# encoder_amplifier2_1layer.net
KiCad netlist of a schematic drawn in EAGLE
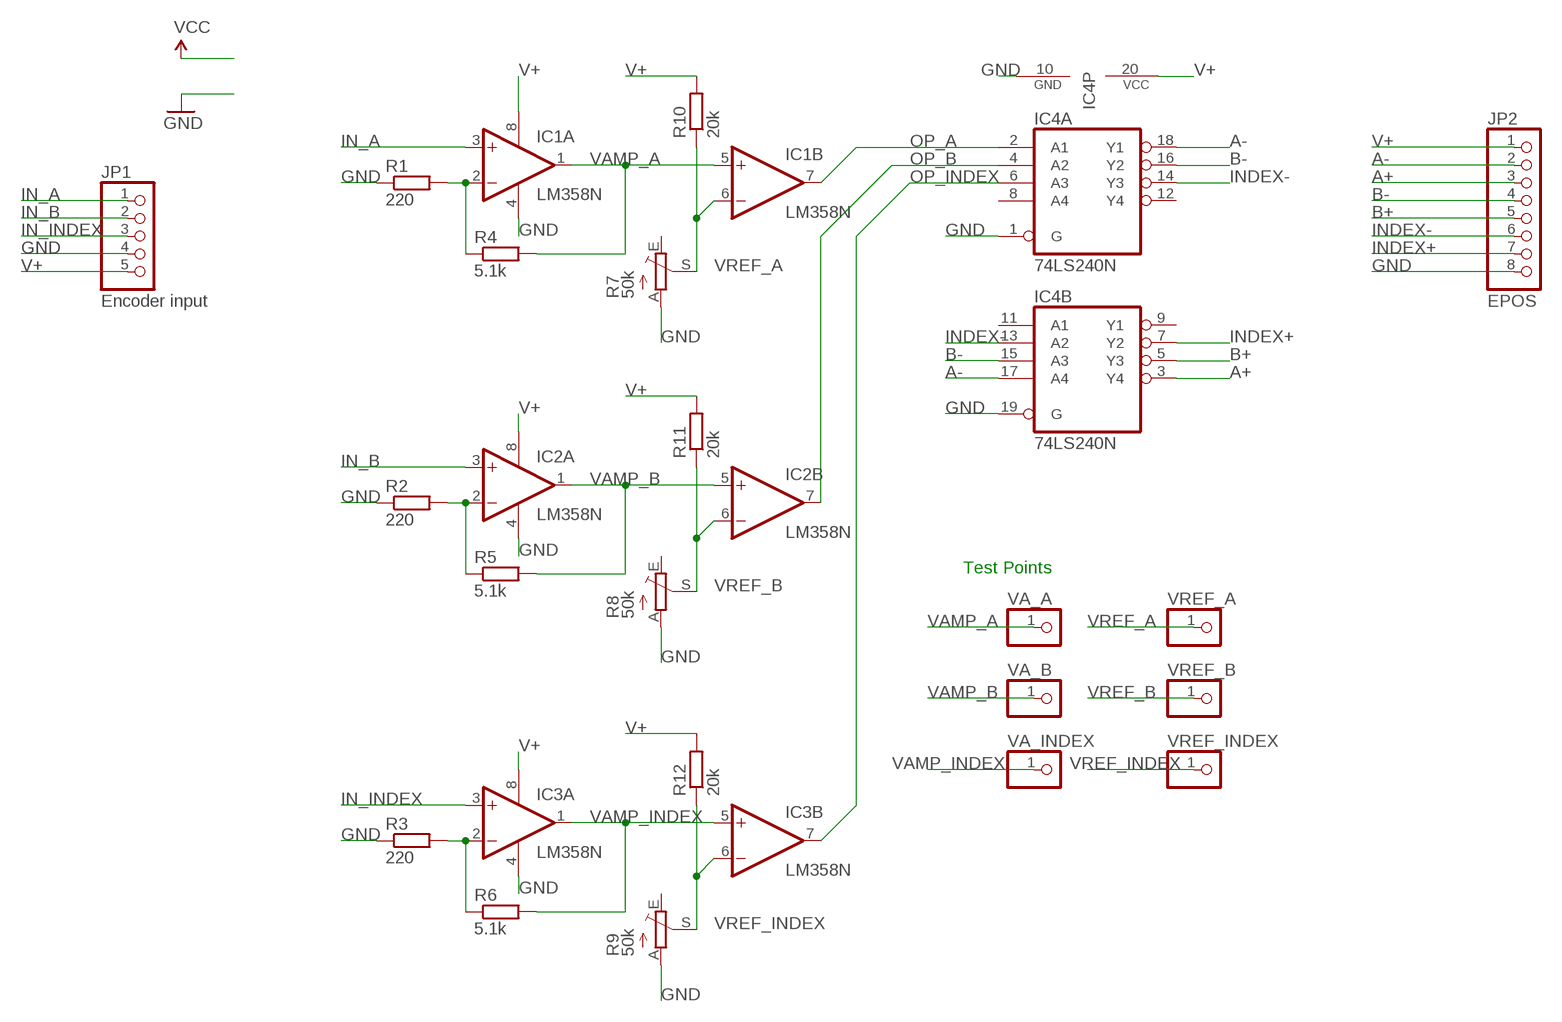
[diagram p0: schematic, sheet 1]

(export (version "E")
  (design (tool "Eeschema 10.0.6"))
  (components
    (comp (ref "IC1")
      (value "LM358N")
      (footprint "eagle-import:DIL08")
      (libsource (lib "eagle-import") (part "LM358N"))
    )
    (comp (ref "IC2")
      (value "LM358N")
      (footprint "eagle-import:DIL08")
      (libsource (lib "eagle-import") (part "LM358N"))
    )
    (comp (ref "IC3")
      (value "LM358N")
      (footprint "eagle-import:DIL08")
      (libsource (lib "eagle-import") (part "LM358N"))
    )
    (comp (ref "IC4")
      (value "74LS240N")
      (footprint "eagle-import:DIL20")
      (libsource (lib "eagle-import") (part "74240NLS"))
    )
    (comp (ref "JP1")
      (value "Encoder input")
      (footprint "eagle-import:1X05")
      (libsource (lib "eagle-import") (part "PINHD-1X5"))
    )
    (comp (ref "JP2")
      (value "EPOS")
      (footprint "eagle-import:1X08")
      (libsource (lib "eagle-import") (part "PINHD-1X8"))
    )
    (comp (ref "R1")
      (value "220")
      (footprint "eagle-import:0204_7")
      (libsource (lib "eagle-import") (part "R-EU_0204/7"))
    )
    (comp (ref "R2")
      (value "220")
      (footprint "eagle-import:0204_7")
      (libsource (lib "eagle-import") (part "R-EU_0204/7"))
    )
    (comp (ref "R3")
      (value "220")
      (footprint "eagle-import:0204_7")
      (libsource (lib "eagle-import") (part "R-EU_0204/7"))
    )
    (comp (ref "R4")
      (value "5.1k")
      (footprint "eagle-import:0204_7")
      (libsource (lib "eagle-import") (part "R-EU_0204/7"))
    )
    (comp (ref "R5")
      (value "5.1k")
      (footprint "eagle-import:0204_7")
      (libsource (lib "eagle-import") (part "R-EU_0204/7"))
    )
    (comp (ref "R6")
      (value "5.1k")
      (footprint "eagle-import:0204_7")
      (libsource (lib "eagle-import") (part "R-EU_0204/7"))
    )
    (comp (ref "R7")
      (value "50k")
      (footprint "eagle-import:LI15")
      (libsource (lib "eagle-import") (part "TRIM_EU-LI15"))
    )
    (comp (ref "R8")
      (value "50k")
      (footprint "eagle-import:LI15")
      (libsource (lib "eagle-import") (part "TRIM_EU-LI15"))
    )
    (comp (ref "R9")
      (value "50k")
      (footprint "eagle-import:LI15")
      (libsource (lib "eagle-import") (part "TRIM_EU-LI15"))
    )
    (comp (ref "R10")
      (value "20k")
      (footprint "eagle-import:0204_7")
      (libsource (lib "eagle-import") (part "R-EU_0204/7"))
    )
    (comp (ref "R11")
      (value "20k")
      (footprint "eagle-import:0204_7")
      (libsource (lib "eagle-import") (part "R-EU_0204/7"))
    )
    (comp (ref "R12")
      (value "20k")
      (footprint "eagle-import:0204_7")
      (libsource (lib "eagle-import") (part "R-EU_0204/7"))
    )
    (comp (ref "VA_A")
      (value "PINHD-1X1")
      (footprint "eagle-import:1X01")
      (libsource (lib "eagle-import") (part "PINHD-1X1"))
    )
    (comp (ref "VA_B")
      (value "PINHD-1X1")
      (footprint "eagle-import:1X01")
      (libsource (lib "eagle-import") (part "PINHD-1X1"))
    )
    (comp (ref "VA_INDEX")
      (value "PINHD-1X1")
      (footprint "eagle-import:1X01")
      (libsource (lib "eagle-import") (part "PINHD-1X1"))
    )
    (comp (ref "VREF_A")
      (value "PINHD-1X1")
      (footprint "eagle-import:1X01")
      (libsource (lib "eagle-import") (part "PINHD-1X1"))
    )
    (comp (ref "VREF_B")
      (value "PINHD-1X1")
      (footprint "eagle-import:1X01")
      (libsource (lib "eagle-import") (part "PINHD-1X1"))
    )
    (comp (ref "VREF_INDEX")
      (value "PINHD-1X1")
      (footprint "eagle-import:1X01")
      (libsource (lib "eagle-import") (part "PINHD-1X1"))
    )
  )
  (nets
    (net (code "1") (name "/A+") (class "Default")
      (node (ref "IC4") (pin "3") (pinfunction "Y4_3") (pintype "tri_state"))
      (node (ref "JP2") (pin "3") (pinfunction "3_3") (pintype "passive"))
    )
    (net (code "2") (name "/A-") (class "Default")
      (node (ref "IC4") (pin "17") (pinfunction "A4_17") (pintype "input"))
      (node (ref "IC4") (pin "18") (pinfunction "Y1_18") (pintype "tri_state"))
      (node (ref "JP2") (pin "2") (pinfunction "2_2") (pintype "passive"))
    )
    (net (code "3") (name "/B+") (class "Default")
      (node (ref "IC4") (pin "5") (pinfunction "Y3_5") (pintype "tri_state"))
      (node (ref "JP2") (pin "5") (pinfunction "5_5") (pintype "passive"))
    )
    (net (code "4") (name "/B-") (class "Default")
      (node (ref "IC4") (pin "15") (pinfunction "A3_15") (pintype "input"))
      (node (ref "IC4") (pin "16") (pinfunction "Y2_16") (pintype "tri_state"))
      (node (ref "JP2") (pin "4") (pinfunction "4_4") (pintype "passive"))
    )
    (net (code "5") (name "/INDEX+") (class "Default")
      (node (ref "IC4") (pin "7") (pinfunction "Y2_7") (pintype "tri_state"))
      (node (ref "JP2") (pin "7") (pinfunction "7_7") (pintype "passive"))
    )
    (net (code "6") (name "/INDEX-") (class "Default")
      (node (ref "IC4") (pin "13") (pinfunction "A2_13") (pintype "input"))
      (node (ref "IC4") (pin "14") (pinfunction "Y3_14") (pintype "tri_state"))
      (node (ref "JP2") (pin "6") (pinfunction "6_6") (pintype "passive"))
    )
    (net (code "7") (name "/IN_A") (class "Default")
      (node (ref "IC1") (pin "3") (pinfunction "+IN_3") (pintype "input"))
      (node (ref "JP1") (pin "1") (pinfunction "1_1") (pintype "passive"))
    )
    (net (code "8") (name "/IN_B") (class "Default")
      (node (ref "IC2") (pin "3") (pinfunction "+IN_3") (pintype "input"))
      (node (ref "JP1") (pin "2") (pinfunction "2_2") (pintype "passive"))
    )
    (net (code "9") (name "/IN_INDEX") (class "Default")
      (node (ref "IC3") (pin "3") (pinfunction "+IN_3") (pintype "input"))
      (node (ref "JP1") (pin "3") (pinfunction "3_3") (pintype "passive"))
    )
    (net (code "10") (name "/OP_A") (class "Default")
      (node (ref "IC1") (pin "7") (pinfunction "OUT_7") (pintype "output"))
      (node (ref "IC4") (pin "2") (pinfunction "A1_2") (pintype "input"))
    )
    (net (code "11") (name "/OP_B") (class "Default")
      (node (ref "IC2") (pin "7") (pinfunction "OUT_7") (pintype "output"))
      (node (ref "IC4") (pin "4") (pinfunction "A2_4") (pintype "input"))
    )
    (net (code "12") (name "/OP_INDEX") (class "Default")
      (node (ref "IC3") (pin "7") (pinfunction "OUT_7") (pintype "output"))
      (node (ref "IC4") (pin "6") (pinfunction "A3_6") (pintype "input"))
    )
    (net (code "13") (name "/V+") (class "Default")
      (node (ref "IC1") (pin "8") (pinfunction "V+_8") (pintype "power_in"))
      (node (ref "IC2") (pin "8") (pinfunction "V+_8") (pintype "power_in"))
      (node (ref "IC3") (pin "8") (pinfunction "V+_8") (pintype "power_in"))
      (node (ref "IC4") (pin "20") (pinfunction "VCC_20") (pintype "power_in"))
      (node (ref "JP1") (pin "5") (pinfunction "5_5") (pintype "passive"))
      (node (ref "JP2") (pin "1") (pinfunction "1_1") (pintype "passive"))
      (node (ref "R10") (pin "2") (pinfunction "2_2") (pintype "passive"))
      (node (ref "R11") (pin "2") (pinfunction "2_2") (pintype "passive"))
      (node (ref "R12") (pin "2") (pinfunction "2_2") (pintype "passive"))
    )
    (net (code "14") (name "/VAMP_A") (class "Default")
      (node (ref "IC1") (pin "1") (pinfunction "OUT_1") (pintype "output"))
      (node (ref "IC1") (pin "5") (pinfunction "+IN_5") (pintype "input"))
      (node (ref "R4") (pin "2") (pinfunction "2_2") (pintype "passive"))
      (node (ref "VA_A") (pin "1") (pinfunction "1_1") (pintype "passive"))
    )
    (net (code "15") (name "/VAMP_B") (class "Default")
      (node (ref "IC2") (pin "1") (pinfunction "OUT_1") (pintype "output"))
      (node (ref "IC2") (pin "5") (pinfunction "+IN_5") (pintype "input"))
      (node (ref "R5") (pin "2") (pinfunction "2_2") (pintype "passive"))
      (node (ref "VA_B") (pin "1") (pinfunction "1_1") (pintype "passive"))
    )
    (net (code "16") (name "/VAMP_INDEX") (class "Default")
      (node (ref "IC3") (pin "1") (pinfunction "OUT_1") (pintype "output"))
      (node (ref "IC3") (pin "5") (pinfunction "+IN_5") (pintype "input"))
      (node (ref "R6") (pin "2") (pinfunction "2_2") (pintype "passive"))
      (node (ref "VA_INDEX") (pin "1") (pinfunction "1_1") (pintype "passive"))
    )
    (net (code "17") (name "/VREF_A") (class "Default")
      (node (ref "IC1") (pin "6") (pinfunction "-IN_6") (pintype "input"))
      (node (ref "R10") (pin "1") (pinfunction "1_1") (pintype "passive"))
      (node (ref "R7") (pin "S") (pinfunction "S_S") (pintype "passive"))
      (node (ref "VREF_A") (pin "1") (pinfunction "1_1") (pintype "passive"))
    )
    (net (code "18") (name "/VREF_B") (class "Default")
      (node (ref "IC2") (pin "6") (pinfunction "-IN_6") (pintype "input"))
      (node (ref "R11") (pin "1") (pinfunction "1_1") (pintype "passive"))
      (node (ref "R8") (pin "S") (pinfunction "S_S") (pintype "passive"))
      (node (ref "VREF_B") (pin "1") (pinfunction "1_1") (pintype "passive"))
    )
    (net (code "19") (name "/VREF_INDEX") (class "Default")
      (node (ref "IC3") (pin "6") (pinfunction "-IN_6") (pintype "input"))
      (node (ref "R12") (pin "1") (pinfunction "1_1") (pintype "passive"))
      (node (ref "R9") (pin "S") (pinfunction "S_S") (pintype "passive"))
      (node (ref "VREF_INDEX") (pin "1") (pinfunction "1_1") (pintype "passive"))
    )
    (net (code "20") (name "GND") (class "Default")
      (node (ref "IC1") (pin "4") (pinfunction "V-_4") (pintype "power_in"))
      (node (ref "IC2") (pin "4") (pinfunction "V-_4") (pintype "power_in"))
      (node (ref "IC3") (pin "4") (pinfunction "V-_4") (pintype "power_in"))
      (node (ref "IC4") (pin "1") (pinfunction "G_1") (pintype "input"))
      (node (ref "IC4") (pin "10") (pinfunction "GND_10") (pintype "power_in"))
      (node (ref "IC4") (pin "19") (pinfunction "G_19") (pintype "input"))
      (node (ref "JP1") (pin "4") (pinfunction "4_4") (pintype "passive"))
      (node (ref "JP2") (pin "8") (pinfunction "8_8") (pintype "passive"))
      (node (ref "R1") (pin "1") (pinfunction "1_1") (pintype "passive"))
      (node (ref "R2") (pin "1") (pinfunction "1_1") (pintype "passive"))
      (node (ref "R3") (pin "1") (pinfunction "1_1") (pintype "passive"))
      (node (ref "R7") (pin "A") (pinfunction "A_A") (pintype "passive"))
      (node (ref "R8") (pin "A") (pinfunction "A_A") (pintype "passive"))
      (node (ref "R9") (pin "A") (pinfunction "A_A") (pintype "passive"))
    )
    (net (code "21") (name "Net-(IC1A--IN)") (class "Default")
      (node (ref "IC1") (pin "2") (pinfunction "-IN_2") (pintype "input"))
      (node (ref "R1") (pin "2") (pinfunction "2_2") (pintype "passive"))
      (node (ref "R4") (pin "1") (pinfunction "1_1") (pintype "passive"))
    )
    (net (code "22") (name "Net-(IC2A--IN)") (class "Default")
      (node (ref "IC2") (pin "2") (pinfunction "-IN_2") (pintype "input"))
      (node (ref "R2") (pin "2") (pinfunction "2_2") (pintype "passive"))
      (node (ref "R5") (pin "1") (pinfunction "1_1") (pintype "passive"))
    )
    (net (code "23") (name "Net-(IC3A--IN)") (class "Default")
      (node (ref "IC3") (pin "2") (pinfunction "-IN_2") (pintype "input"))
      (node (ref "R3") (pin "2") (pinfunction "2_2") (pintype "passive"))
      (node (ref "R6") (pin "1") (pinfunction "1_1") (pintype "passive"))
    )
    (net (code "25") (name "unconnected-(IC4A-A4-Pad8)") (class "Default")
      (node (ref "IC4") (pin "8") (pinfunction "A4_8") (pintype "input"))
    )
    (net (code "26") (name "unconnected-(IC4A-Y4-Pad12)") (class "Default")
      (node (ref "IC4") (pin "12") (pinfunction "Y4_12") (pintype "tri_state"))
    )
    (net (code "27") (name "unconnected-(IC4B-A1-Pad11)") (class "Default")
      (node (ref "IC4") (pin "11") (pinfunction "A1_11") (pintype "input"))
    )
    (net (code "28") (name "unconnected-(IC4B-Y1-Pad9)") (class "Default")
      (node (ref "IC4") (pin "9") (pinfunction "Y1_9") (pintype "tri_state"))
    )
    (net (code "29") (name "unconnected-(R7-PadE)") (class "Default")
      (node (ref "R7") (pin "E") (pinfunction "E_E") (pintype "passive"))
    )
    (net (code "30") (name "unconnected-(R8-PadE)") (class "Default")
      (node (ref "R8") (pin "E") (pinfunction "E_E") (pintype "passive"))
    )
    (net (code "31") (name "unconnected-(R9-PadE)") (class "Default")
      (node (ref "R9") (pin "E") (pinfunction "E_E") (pintype "passive"))
    )
  )
)
